# 2_Sensors.net
KiCad netlist of a schematic drawn in Altium Designer
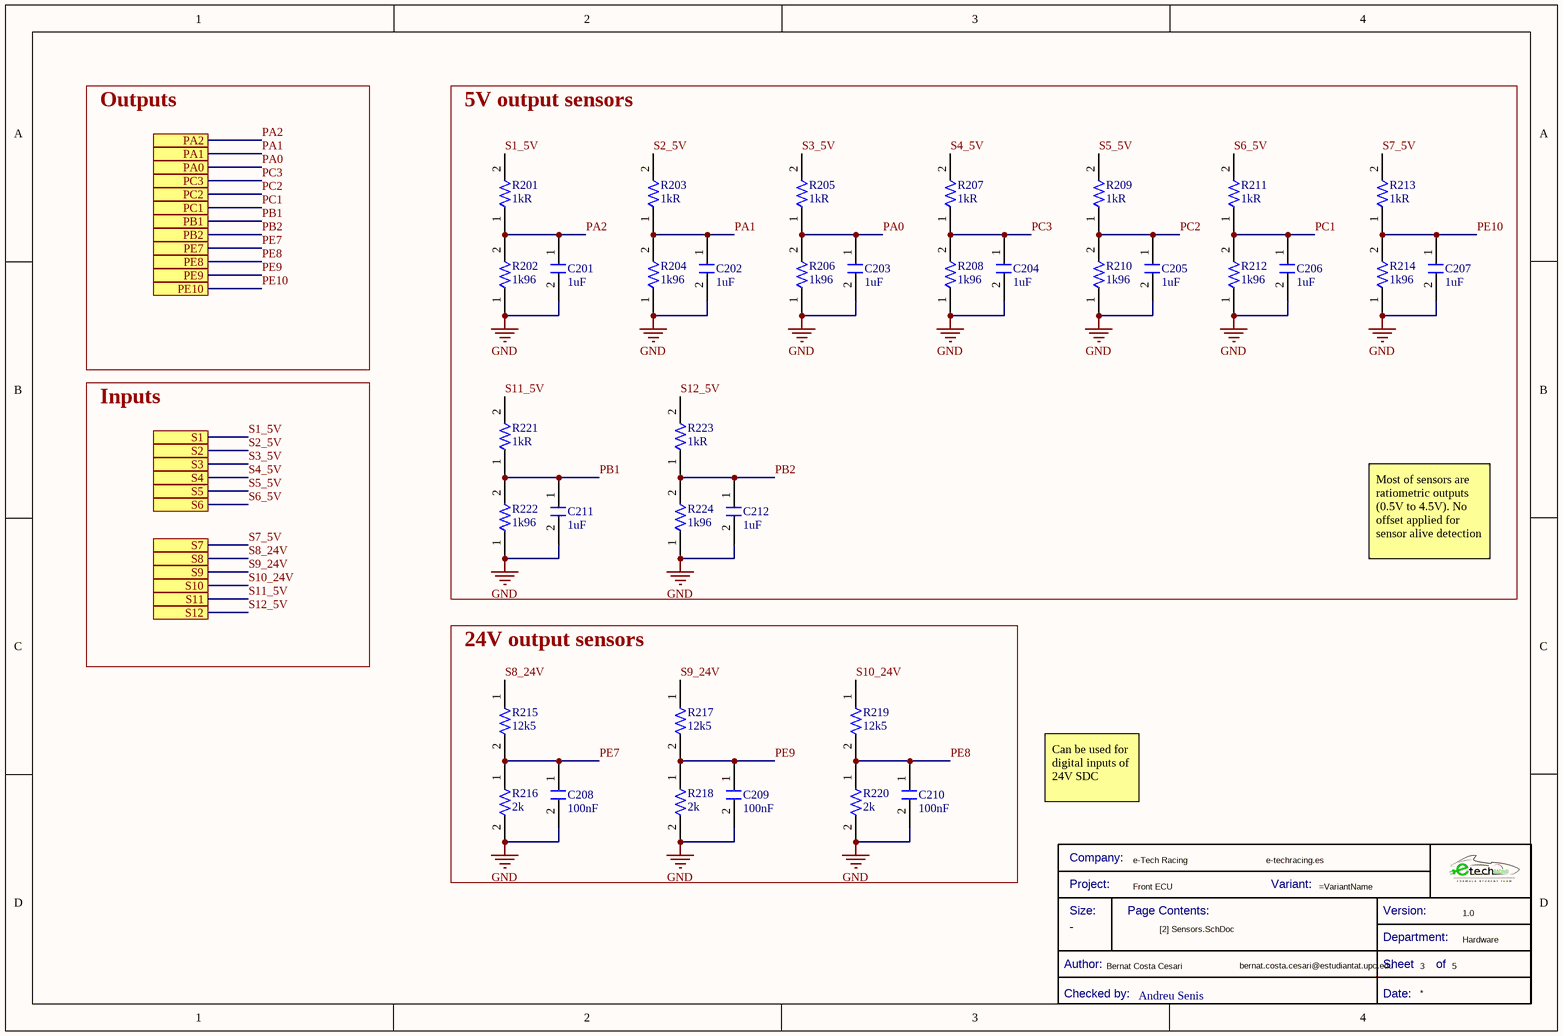
[diagram p0: [2] Sensors.SchDoc]

(export (version "E")
  (design (tool "Eeschema 10.0.6"))
  (components
    (comp (ref "C201")
      (value "885012207103")
      (footprint "C0805FNPC-R")
      (fields
        (field (name "TOLERANCE") "10%")
        (field (name "CAPACITANCE") "1uF")
        (field (name ".CREATOR") "GP")
      )
      (libsource (lib "Passives") (part "C1u-50V-0805FNPC-X7R"))
    )
    (comp (ref "C202")
      (value "885012207103")
      (footprint "C0805FNPC-R")
      (fields
        (field (name "TOLERANCE") "10%")
        (field (name "CAPACITANCE") "1uF")
        (field (name ".CREATOR") "GP")
      )
      (libsource (lib "Passives") (part "C1u-50V-0805FNPC-X7R"))
    )
    (comp (ref "C203")
      (value "885012207103")
      (footprint "C0805FNPC-R")
      (fields
        (field (name "TOLERANCE") "10%")
        (field (name "CAPACITANCE") "1uF")
        (field (name ".CREATOR") "GP")
      )
      (libsource (lib "Passives") (part "C1u-50V-0805FNPC-X7R"))
    )
    (comp (ref "C204")
      (value "885012207103")
      (footprint "C0805FNPC-R")
      (fields
        (field (name "TOLERANCE") "10%")
        (field (name "CAPACITANCE") "1uF")
        (field (name ".CREATOR") "GP")
      )
      (libsource (lib "Passives") (part "C1u-50V-0805FNPC-X7R"))
    )
    (comp (ref "C205")
      (value "885012207103")
      (footprint "C0805FNPC-R")
      (fields
        (field (name "TOLERANCE") "10%")
        (field (name "CAPACITANCE") "1uF")
        (field (name ".CREATOR") "GP")
      )
      (libsource (lib "Passives") (part "C1u-50V-0805FNPC-X7R"))
    )
    (comp (ref "C206")
      (value "885012207103")
      (footprint "C0805FNPC-R")
      (fields
        (field (name "TOLERANCE") "10%")
        (field (name "CAPACITANCE") "1uF")
        (field (name ".CREATOR") "GP")
      )
      (libsource (lib "Passives") (part "C1u-50V-0805FNPC-X7R"))
    )
    (comp (ref "C207")
      (value "885012207103")
      (footprint "C0805FNPC-R")
      (fields
        (field (name "TOLERANCE") "10%")
        (field (name "CAPACITANCE") "1uF")
        (field (name ".CREATOR") "GP")
      )
      (libsource (lib "Passives") (part "C1u-50V-0805FNPC-X7R"))
    )
    (comp (ref "C208")
      (value "885012207098")
      (footprint "C0805FNPC-R")
      (description "Cap, 0.1ΜF, 50V, 10%, X7R, 0805")
      (fields
        (field (name "TOLERANCE") "10%")
        (field (name "CAPACITANCE") "100nF")
        (field (name ".CREATOR") "DR")
      )
      (libsource (lib "Passives") (part "C100n-50V-0805FNPC-X7R"))
    )
    (comp (ref "C209")
      (value "885012207098")
      (footprint "C0805FNPC-R")
      (description "Cap, 0.1ΜF, 50V, 10%, X7R, 0805")
      (fields
        (field (name "TOLERANCE") "10%")
        (field (name "CAPACITANCE") "100nF")
        (field (name ".CREATOR") "DR")
      )
      (libsource (lib "Passives") (part "C100n-50V-0805FNPC-X7R"))
    )
    (comp (ref "C210")
      (value "885012207098")
      (footprint "C0805FNPC-R")
      (description "Cap, 0.1ΜF, 50V, 10%, X7R, 0805")
      (fields
        (field (name "TOLERANCE") "10%")
        (field (name "CAPACITANCE") "100nF")
        (field (name ".CREATOR") "DR")
      )
      (libsource (lib "Passives") (part "C100n-50V-0805FNPC-X7R"))
    )
    (comp (ref "C211")
      (value "885012207103")
      (footprint "C0805FNPC-R")
      (fields
        (field (name "TOLERANCE") "10%")
        (field (name "CAPACITANCE") "1uF")
        (field (name ".CREATOR") "GP")
      )
      (libsource (lib "Passives") (part "C1u-50V-0805FNPC-X7R"))
    )
    (comp (ref "C212")
      (value "885012207103")
      (footprint "C0805FNPC-R")
      (fields
        (field (name "TOLERANCE") "10%")
        (field (name "CAPACITANCE") "1uF")
        (field (name ".CREATOR") "GP")
      )
      (libsource (lib "Passives") (part "C1u-50V-0805FNPC-X7R"))
    )
    (comp (ref "R201")
      (value "CR0805-JW-102ELF")
      (footprint "R0805FTK")
      (description "Res Thick Film 0805 1K Ohm 5% 1/8W ±200ppm/°C Molded SMD SMD Paper Tape on Plastic Reel")
      (fields
        (field (name "TOLERANCE") "5%")
        (field (name "RESISTANCE") "1kR")
        (field (name ".CREATOR") "GP")
      )
      (libsource (lib "Passives") (part "R1k-0805FTK"))
    )
    (comp (ref "R202")
      (value "1k96")
      (footprint "R0805FTK")
      (libsource (lib "Passives") (part "R1k96-0805FTK"))
    )
    (comp (ref "R203")
      (value "CR0805-JW-102ELF")
      (footprint "R0805FTK")
      (description "Res Thick Film 0805 1K Ohm 5% 1/8W ±200ppm/°C Molded SMD SMD Paper Tape on Plastic Reel")
      (fields
        (field (name "TOLERANCE") "5%")
        (field (name "RESISTANCE") "1kR")
        (field (name ".CREATOR") "GP")
      )
      (libsource (lib "Passives") (part "R1k-0805FTK"))
    )
    (comp (ref "R204")
      (value "1k96")
      (footprint "R0805FTK")
      (libsource (lib "Passives") (part "R1k96-0805FTK"))
    )
    (comp (ref "R205")
      (value "CR0805-JW-102ELF")
      (footprint "R0805FTK")
      (description "Res Thick Film 0805 1K Ohm 5% 1/8W ±200ppm/°C Molded SMD SMD Paper Tape on Plastic Reel")
      (fields
        (field (name "TOLERANCE") "5%")
        (field (name "RESISTANCE") "1kR")
        (field (name ".CREATOR") "GP")
      )
      (libsource (lib "Passives") (part "R1k-0805FTK"))
    )
    (comp (ref "R206")
      (value "1k96")
      (footprint "R0805FTK")
      (libsource (lib "Passives") (part "R1k96-0805FTK"))
    )
    (comp (ref "R207")
      (value "CR0805-JW-102ELF")
      (footprint "R0805FTK")
      (description "Res Thick Film 0805 1K Ohm 5% 1/8W ±200ppm/°C Molded SMD SMD Paper Tape on Plastic Reel")
      (fields
        (field (name "TOLERANCE") "5%")
        (field (name "RESISTANCE") "1kR")
        (field (name ".CREATOR") "GP")
      )
      (libsource (lib "Passives") (part "R1k-0805FTK"))
    )
    (comp (ref "R208")
      (value "1k96")
      (footprint "R0805FTK")
      (libsource (lib "Passives") (part "R1k96-0805FTK"))
    )
    (comp (ref "R209")
      (value "CR0805-JW-102ELF")
      (footprint "R0805FTK")
      (description "Res Thick Film 0805 1K Ohm 5% 1/8W ±200ppm/°C Molded SMD SMD Paper Tape on Plastic Reel")
      (fields
        (field (name "TOLERANCE") "5%")
        (field (name "RESISTANCE") "1kR")
        (field (name ".CREATOR") "GP")
      )
      (libsource (lib "Passives") (part "R1k-0805FTK"))
    )
    (comp (ref "R210")
      (value "1k96")
      (footprint "R0805FTK")
      (libsource (lib "Passives") (part "R1k96-0805FTK"))
    )
    (comp (ref "R211")
      (value "CR0805-JW-102ELF")
      (footprint "R0805FTK")
      (description "Res Thick Film 0805 1K Ohm 5% 1/8W ±200ppm/°C Molded SMD SMD Paper Tape on Plastic Reel")
      (fields
        (field (name "TOLERANCE") "5%")
        (field (name "RESISTANCE") "1kR")
        (field (name ".CREATOR") "GP")
      )
      (libsource (lib "Passives") (part "R1k-0805FTK"))
    )
    (comp (ref "R212")
      (value "1k96")
      (footprint "R0805FTK")
      (libsource (lib "Passives") (part "R1k96-0805FTK"))
    )
    (comp (ref "R213")
      (value "CR0805-JW-102ELF")
      (footprint "R0805FTK")
      (description "Res Thick Film 0805 1K Ohm 5% 1/8W ±200ppm/°C Molded SMD SMD Paper Tape on Plastic Reel")
      (fields
        (field (name "TOLERANCE") "5%")
        (field (name "RESISTANCE") "1kR")
        (field (name ".CREATOR") "GP")
      )
      (libsource (lib "Passives") (part "R1k-0805FTK"))
    )
    (comp (ref "R214")
      (value "1k96")
      (footprint "R0805FTK")
      (libsource (lib "Passives") (part "R1k96-0805FTK"))
    )
    (comp (ref "R215")
      (value "12k5")
      (footprint "R0805FTK")
      (libsource (lib "Passives") (part "R12k5-0805FTK"))
    )
    (comp (ref "R216") (value "2k") (footprint "R0805FTK") (libsource (lib "Passives") (part "R2k-0805FTK")))
    (comp (ref "R217")
      (value "12k5")
      (footprint "R0805FTK")
      (libsource (lib "Passives") (part "R12k5-0805FTK"))
    )
    (comp (ref "R218") (value "2k") (footprint "R0805FTK") (libsource (lib "Passives") (part "R2k-0805FTK")))
    (comp (ref "R219")
      (value "12k5")
      (footprint "R0805FTK")
      (libsource (lib "Passives") (part "R12k5-0805FTK"))
    )
    (comp (ref "R220") (value "2k") (footprint "R0805FTK") (libsource (lib "Passives") (part "R2k-0805FTK")))
    (comp (ref "R221")
      (value "CR0805-JW-102ELF")
      (footprint "R0805FTK")
      (description "Res Thick Film 0805 1K Ohm 5% 1/8W ±200ppm/°C Molded SMD SMD Paper Tape on Plastic Reel")
      (fields
        (field (name "TOLERANCE") "5%")
        (field (name "RESISTANCE") "1kR")
        (field (name ".CREATOR") "GP")
      )
      (libsource (lib "Passives") (part "R1k-0805FTK"))
    )
    (comp (ref "R222")
      (value "1k96")
      (footprint "R0805FTK")
      (libsource (lib "Passives") (part "R1k96-0805FTK"))
    )
    (comp (ref "R223")
      (value "CR0805-JW-102ELF")
      (footprint "R0805FTK")
      (description "Res Thick Film 0805 1K Ohm 5% 1/8W ±200ppm/°C Molded SMD SMD Paper Tape on Plastic Reel")
      (fields
        (field (name "TOLERANCE") "5%")
        (field (name "RESISTANCE") "1kR")
        (field (name ".CREATOR") "GP")
      )
      (libsource (lib "Passives") (part "R1k-0805FTK"))
    )
    (comp (ref "R224")
      (value "1k96")
      (footprint "R0805FTK")
      (libsource (lib "Passives") (part "R1k96-0805FTK"))
    )
  )
  (nets
    (net (code "1") (name "/PA0") (class "Default")
      (node (ref "C203") (pin "1") (pinfunction "1_1") (pintype "passive"))
      (node (ref "R205") (pin "1") (pinfunction "1_1") (pintype "passive"))
      (node (ref "R206") (pin "2") (pinfunction "2_2") (pintype "passive"))
    )
    (net (code "2") (name "/PA1") (class "Default")
      (node (ref "C202") (pin "1") (pinfunction "1_1") (pintype "passive"))
      (node (ref "R203") (pin "1") (pinfunction "1_1") (pintype "passive"))
      (node (ref "R204") (pin "2") (pinfunction "2_2") (pintype "passive"))
    )
    (net (code "3") (name "/PA2") (class "Default")
      (node (ref "C201") (pin "1") (pinfunction "1_1") (pintype "passive"))
      (node (ref "R201") (pin "1") (pinfunction "1_1") (pintype "passive"))
      (node (ref "R202") (pin "2") (pinfunction "2_2") (pintype "passive"))
    )
    (net (code "4") (name "/PB1") (class "Default")
      (node (ref "C211") (pin "1") (pinfunction "1_1") (pintype "passive"))
      (node (ref "R221") (pin "1") (pinfunction "1_1") (pintype "passive"))
      (node (ref "R222") (pin "2") (pinfunction "2_2") (pintype "passive"))
    )
    (net (code "5") (name "/PB2") (class "Default")
      (node (ref "C212") (pin "1") (pinfunction "1_1") (pintype "passive"))
      (node (ref "R223") (pin "1") (pinfunction "1_1") (pintype "passive"))
      (node (ref "R224") (pin "2") (pinfunction "2_2") (pintype "passive"))
    )
    (net (code "6") (name "/PC1") (class "Default")
      (node (ref "C206") (pin "1") (pinfunction "1_1") (pintype "passive"))
      (node (ref "R211") (pin "1") (pinfunction "1_1") (pintype "passive"))
      (node (ref "R212") (pin "2") (pinfunction "2_2") (pintype "passive"))
    )
    (net (code "7") (name "/PC2") (class "Default")
      (node (ref "C205") (pin "1") (pinfunction "1_1") (pintype "passive"))
      (node (ref "R209") (pin "1") (pinfunction "1_1") (pintype "passive"))
      (node (ref "R210") (pin "2") (pinfunction "2_2") (pintype "passive"))
    )
    (net (code "8") (name "/PC3") (class "Default")
      (node (ref "C204") (pin "1") (pinfunction "1_1") (pintype "passive"))
      (node (ref "R207") (pin "1") (pinfunction "1_1") (pintype "passive"))
      (node (ref "R208") (pin "2") (pinfunction "2_2") (pintype "passive"))
    )
    (net (code "9") (name "/PE7") (class "Default")
      (node (ref "C208") (pin "1") (pinfunction "1_1") (pintype "passive"))
      (node (ref "R215") (pin "2") (pinfunction "2_2") (pintype "passive"))
      (node (ref "R216") (pin "1") (pinfunction "1_1") (pintype "passive"))
    )
    (net (code "10") (name "/PE8") (class "Default")
      (node (ref "C210") (pin "1") (pinfunction "1_1") (pintype "passive"))
      (node (ref "R219") (pin "2") (pinfunction "2_2") (pintype "passive"))
      (node (ref "R220") (pin "1") (pinfunction "1_1") (pintype "passive"))
    )
    (net (code "11") (name "/PE9") (class "Default")
      (node (ref "C209") (pin "1") (pinfunction "1_1") (pintype "passive"))
      (node (ref "R217") (pin "2") (pinfunction "2_2") (pintype "passive"))
      (node (ref "R218") (pin "1") (pinfunction "1_1") (pintype "passive"))
    )
    (net (code "12") (name "/PE10") (class "Default")
      (node (ref "C207") (pin "1") (pinfunction "1_1") (pintype "passive"))
      (node (ref "R213") (pin "1") (pinfunction "1_1") (pintype "passive"))
      (node (ref "R214") (pin "2") (pinfunction "2_2") (pintype "passive"))
    )
    (net (code "13") (name "/S1_5V") (class "Default")
      (node (ref "R201") (pin "2") (pinfunction "2_2") (pintype "passive"))
    )
    (net (code "14") (name "/S2_5V") (class "Default")
      (node (ref "R203") (pin "2") (pinfunction "2_2") (pintype "passive"))
    )
    (net (code "15") (name "/S3_5V") (class "Default")
      (node (ref "R205") (pin "2") (pinfunction "2_2") (pintype "passive"))
    )
    (net (code "16") (name "/S4_5V") (class "Default")
      (node (ref "R207") (pin "2") (pinfunction "2_2") (pintype "passive"))
    )
    (net (code "17") (name "/S5_5V") (class "Default")
      (node (ref "R209") (pin "2") (pinfunction "2_2") (pintype "passive"))
    )
    (net (code "18") (name "/S6_5V") (class "Default")
      (node (ref "R211") (pin "2") (pinfunction "2_2") (pintype "passive"))
    )
    (net (code "19") (name "/S7_5V") (class "Default")
      (node (ref "R213") (pin "2") (pinfunction "2_2") (pintype "passive"))
    )
    (net (code "20") (name "/S8_24V") (class "Default")
      (node (ref "R215") (pin "1") (pinfunction "1_1") (pintype "passive"))
    )
    (net (code "21") (name "/S9_24V") (class "Default")
      (node (ref "R217") (pin "1") (pinfunction "1_1") (pintype "passive"))
    )
    (net (code "22") (name "/S10_24V") (class "Default")
      (node (ref "R219") (pin "1") (pinfunction "1_1") (pintype "passive"))
    )
    (net (code "23") (name "/S11_5V") (class "Default")
      (node (ref "R221") (pin "2") (pinfunction "2_2") (pintype "passive"))
    )
    (net (code "24") (name "/S12_5V") (class "Default")
      (node (ref "R223") (pin "2") (pinfunction "2_2") (pintype "passive"))
    )
    (net (code "25") (name "GND") (class "Default")
      (node (ref "C201") (pin "2") (pinfunction "2_2") (pintype "passive"))
      (node (ref "C202") (pin "2") (pinfunction "2_2") (pintype "passive"))
      (node (ref "C203") (pin "2") (pinfunction "2_2") (pintype "passive"))
      (node (ref "C204") (pin "2") (pinfunction "2_2") (pintype "passive"))
      (node (ref "C205") (pin "2") (pinfunction "2_2") (pintype "passive"))
      (node (ref "C206") (pin "2") (pinfunction "2_2") (pintype "passive"))
      (node (ref "C207") (pin "2") (pinfunction "2_2") (pintype "passive"))
      (node (ref "C208") (pin "2") (pinfunction "2_2") (pintype "passive"))
      (node (ref "C209") (pin "2") (pinfunction "2_2") (pintype "passive"))
      (node (ref "C210") (pin "2") (pinfunction "2_2") (pintype "passive"))
      (node (ref "C211") (pin "2") (pinfunction "2_2") (pintype "passive"))
      (node (ref "C212") (pin "2") (pinfunction "2_2") (pintype "passive"))
      (node (ref "R202") (pin "1") (pinfunction "1_1") (pintype "passive"))
      (node (ref "R204") (pin "1") (pinfunction "1_1") (pintype "passive"))
      (node (ref "R206") (pin "1") (pinfunction "1_1") (pintype "passive"))
      (node (ref "R208") (pin "1") (pinfunction "1_1") (pintype "passive"))
      (node (ref "R210") (pin "1") (pinfunction "1_1") (pintype "passive"))
      (node (ref "R212") (pin "1") (pinfunction "1_1") (pintype "passive"))
      (node (ref "R214") (pin "1") (pinfunction "1_1") (pintype "passive"))
      (node (ref "R216") (pin "2") (pinfunction "2_2") (pintype "passive"))
      (node (ref "R218") (pin "2") (pinfunction "2_2") (pintype "passive"))
      (node (ref "R220") (pin "2") (pinfunction "2_2") (pintype "passive"))
      (node (ref "R222") (pin "1") (pinfunction "1_1") (pintype "passive"))
      (node (ref "R224") (pin "1") (pinfunction "1_1") (pintype "passive"))
    )
  )
)
